# POTS.net
KiCad netlist of a schematic drawn in Altium Designer
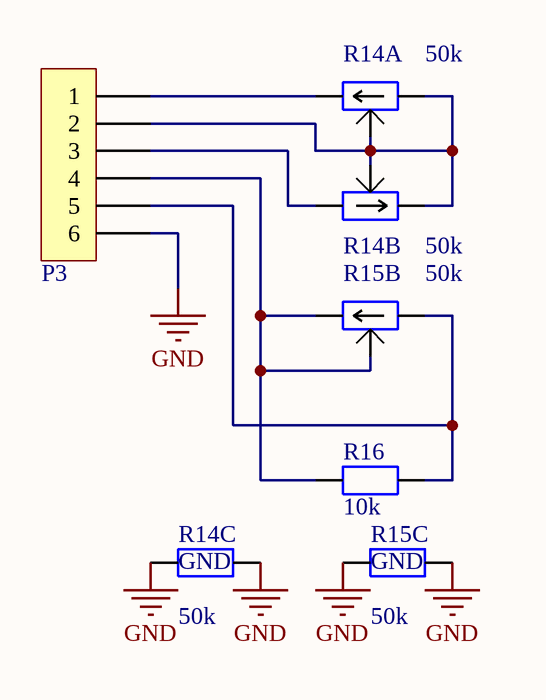
[diagram p0: POTS.SchDoc]

(export (version "E")
  (design (tool "Eeschema 10.0.6"))
  (components
    (comp (ref "P3")
      (value "SIL-CONN-6")
      (footprint "SIL-CONN-6-R1")
      (libsource (lib "SchLib1") (part "SIL-CONN-6"))
    )
    (comp (ref "R14")
      (value "50k")
      (footprint "RK09L12B0A31")
      (fields (field (name "Comment") "RK09L12B0A31"))
      (libsource (lib "") (part "RK09L12B0A31_2"))
    )
    (comp (ref "R15")
      (value "50k")
      (footprint "RK09L12B0A31")
      (fields (field (name "Comment") "RK09L12B0A31"))
      (libsource (lib "") (part "RK09L12B0A31_1"))
    )
    (comp (ref "R16")
      (value "10k")
      (footprint "0805_Resistor")
      (fields (field (name "Comment") "Resistor"))
      (libsource (lib "SchLib1") (part "Resistor"))
    )
  )
  (nets
    (net (code "1") (name "GND") (class "Default")
      (node (ref "P3") (pin "6") (pinfunction "6_6") (pintype "passive"))
      (node (ref "R14") (pin "7") (pinfunction "7_7") (pintype "passive"))
      (node (ref "R14") (pin "8") (pinfunction "8_8") (pintype "passive"))
      (node (ref "R15") (pin "7") (pinfunction "7_7") (pintype "passive"))
      (node (ref "R15") (pin "8") (pinfunction "8_8") (pintype "passive"))
    )
    (net (code "2") (name "Net-(P3-Pad1)") (class "Default")
      (node (ref "P3") (pin "1") (pinfunction "1_1") (pintype "passive"))
      (node (ref "R14") (pin "3") (pinfunction "3_3") (pintype "passive"))
    )
    (net (code "3") (name "Net-(P3-Pad2)") (class "Default")
      (node (ref "P3") (pin "2") (pinfunction "2_2") (pintype "passive"))
      (node (ref "R14") (pin "1") (pinfunction "1_1") (pintype "passive"))
      (node (ref "R14") (pin "2") (pinfunction "2_2") (pintype "passive"))
      (node (ref "R14") (pin "5") (pinfunction "5_5") (pintype "passive"))
      (node (ref "R14") (pin "6") (pinfunction "6_6") (pintype "passive"))
    )
    (net (code "4") (name "Net-(P3-Pad3)") (class "Default")
      (node (ref "P3") (pin "3") (pinfunction "3_3") (pintype "passive"))
      (node (ref "R14") (pin "4") (pinfunction "4_4") (pintype "passive"))
    )
    (net (code "5") (name "Net-(P3-Pad4)") (class "Default")
      (node (ref "P3") (pin "4") (pinfunction "4_4") (pintype "passive"))
      (node (ref "R15") (pin "5") (pinfunction "5_5") (pintype "passive"))
      (node (ref "R15") (pin "6") (pinfunction "6_6") (pintype "passive"))
      (node (ref "R16") (pin "1") (pinfunction "1_1") (pintype "passive"))
    )
    (net (code "6") (name "Net-(P3-Pad5)") (class "Default")
      (node (ref "P3") (pin "5") (pinfunction "5_5") (pintype "passive"))
      (node (ref "R15") (pin "4") (pinfunction "4_4") (pintype "passive"))
      (node (ref "R16") (pin "2") (pinfunction "2_2") (pintype "passive"))
    )
  )
)
